# main.net
KiCad netlist of a schematic drawn in Altium Designer
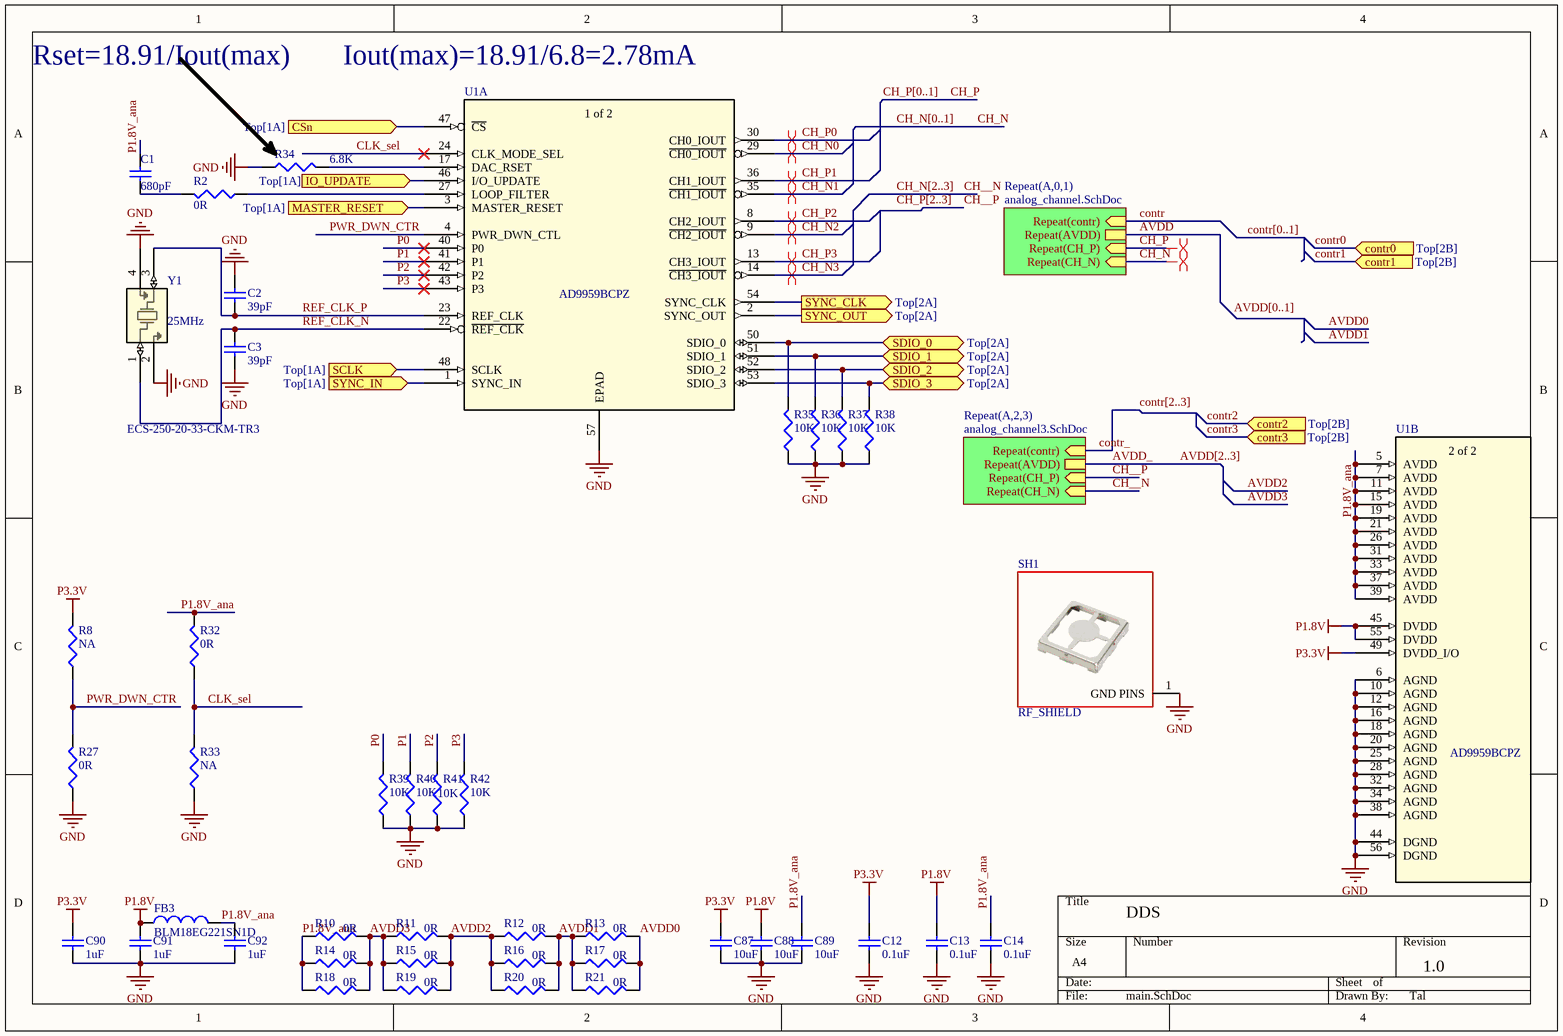
[diagram p0: main.SchDoc]

(export (version "E")
  (design (tool "Eeschema 10.0.6"))
  (components
    (comp (ref "C1")
      (value "680pF 50V")
      (footprint "C0402")
      (description "CAP CER 680PF 50V NP0 0402")
      (fields
        (field (name "MANUFACTURER PART NUMBER") "C1005C0G1H6R8D")
        (field (name "MANUFACTURER") "TDK Corporation")
        (field (name "CAPACITANCE") "680pF")
      )
      (libsource (lib "L_SCH_C") (part "CAP CER 6.8pF 50V NP0 0402"))
    )
    (comp (ref "C2")
      (value "39pF 50V")
      (footprint "C0402")
      (description "CAP CER 39PF 50V NP0 0402")
      (fields
        (field (name "MANUFACTURER PART NUMBER") "C1005C0G1H6R8D")
        (field (name "MANUFACTURER") "TDK Corporation")
        (field (name "CAPACITANCE") "39pF")
      )
      (libsource (lib "L_SCH_C") (part "CAP CER 6.8pF 50V NP0 0402"))
    )
    (comp (ref "C3")
      (value "39pF 50V")
      (footprint "C0402")
      (description "CAP CER 39PF 50V NP0 0402")
      (fields
        (field (name "MANUFACTURER PART NUMBER") "C1005C0G1H6R8D")
        (field (name "MANUFACTURER") "TDK Corporation")
        (field (name "CAPACITANCE") "39pF")
      )
      (libsource (lib "L_SCH_C") (part "CAP CER 6.8pF 50V NP0 0402"))
    )
    (comp (ref "C12")
      (value "0.1uF 50V")
      (footprint "C0402")
      (description "CAP CER 0.1uF 50V NP0 0402")
      (fields
        (field (name "MANUFACTURER PART NUMBER") "C1005C0G1H6R8D")
        (field (name "MANUFACTURER") "TDK Corporation")
        (field (name "CAPACITANCE") "0.1uF")
      )
      (libsource (lib "L_SCH_C") (part "CAP CER 6.8pF 50V NP0 0402"))
    )
    (comp (ref "C13")
      (value "0.1uF 50V")
      (footprint "C0402")
      (description "CAP CER 0.1uF 50V NP0 0402")
      (fields
        (field (name "MANUFACTURER PART NUMBER") "C1005C0G1H6R8D")
        (field (name "MANUFACTURER") "TDK Corporation")
        (field (name "CAPACITANCE") "0.1uF")
      )
      (libsource (lib "L_SCH_C") (part "CAP CER 6.8pF 50V NP0 0402"))
    )
    (comp (ref "C14")
      (value "0.1uF 50V")
      (footprint "C0402")
      (description "CAP CER 0.1uF 50V NP0 0402")
      (fields
        (field (name "MANUFACTURER PART NUMBER") "C1005C0G1H6R8D")
        (field (name "MANUFACTURER") "TDK Corporation")
        (field (name "CAPACITANCE") "0.1uF")
      )
      (libsource (lib "L_SCH_C") (part "CAP CER 6.8pF 50V NP0 0402"))
    )
    (comp (ref "C87")
      (value "10uF 10V")
      (footprint "C0402")
      (description "CAP CER 10uF 10V X5R 0402")
      (fields
        (field (name "MANUFACTURER PART NUMBER") "C1005C0G1H6R8D")
        (field (name "MANUFACTURER") "TDK Corporation")
        (field (name "CAPACITANCE") "10uF")
      )
      (libsource (lib "L_SCH_C") (part "CAP CER 6.8pF 50V NP0 0402"))
    )
    (comp (ref "C88")
      (value "10uF 10V")
      (footprint "C0402")
      (description "CAP CER 10uF 10V X5R 0402")
      (fields
        (field (name "MANUFACTURER PART NUMBER") "C1005C0G1H6R8D")
        (field (name "MANUFACTURER") "TDK Corporation")
        (field (name "CAPACITANCE") "10uF")
      )
      (libsource (lib "L_SCH_C") (part "CAP CER 6.8pF 50V NP0 0402"))
    )
    (comp (ref "C89")
      (value "10uF 10V")
      (footprint "C0402")
      (description "CAP CER 10uF 10V X5R 0402")
      (fields
        (field (name "MANUFACTURER PART NUMBER") "C1005C0G1H6R8D")
        (field (name "MANUFACTURER") "TDK Corporation")
        (field (name "CAPACITANCE") "10uF")
      )
      (libsource (lib "L_SCH_C") (part "CAP CER 6.8pF 50V NP0 0402"))
    )
    (comp (ref "C90")
      (value "1uF 25V")
      (footprint "C0402")
      (description "CAP CER 1uF 25V X5R 0402")
      (fields
        (field (name "MANUFACTURER PART NUMBER") "C1005C0G1H6R8D")
        (field (name "MANUFACTURER") "TDK Corporation")
        (field (name "CAPACITANCE") "1uF")
      )
      (libsource (lib "L_SCH_C") (part "CAP CER 6.8pF 50V NP0 0402"))
    )
    (comp (ref "C91")
      (value "1uF 25V")
      (footprint "C0402")
      (description "CAP CER 1uF 25V X5R 0402")
      (fields
        (field (name "MANUFACTURER PART NUMBER") "C1005C0G1H6R8D")
        (field (name "MANUFACTURER") "TDK Corporation")
        (field (name "CAPACITANCE") "1uF")
      )
      (libsource (lib "L_SCH_C") (part "CAP CER 6.8pF 50V NP0 0402"))
    )
    (comp (ref "C92")
      (value "1uF 25V")
      (footprint "C0402")
      (description "CAP CER 1uF 25V X5R 0402")
      (fields
        (field (name "MANUFACTURER PART NUMBER") "C1005C0G1H6R8D")
        (field (name "MANUFACTURER") "TDK Corporation")
        (field (name "CAPACITANCE") "1uF")
      )
      (libsource (lib "L_SCH_C") (part "CAP CER 6.8pF 50V NP0 0402"))
    )
    (comp (ref "FB3")
      (value "BLM18EG221SN1D")
      (footprint "fb0603")
      (description "FERRITE BEAD 220_OHM@100MHz 0603 2A 50mohm_DC")
      (fields
        (field (name "MANUFACTURER") "Taiyo Yuden")
        (field (name "MANUFACTURER PART NUMBER") "BLM18EG221SN1D")
      )
      (libsource (lib "L_SCH") (part "BK1608HS600-T"))
    )
    (comp (ref "R2")
      (value "0R")
      (footprint "R0402")
      (description "RES 0 OHM 1/10W 1% 0402 SMD")
      (fields
        (field (name "MANUFACTURER PART NUMBER") "ERJ-2RKF1000X")
        (field (name "MANUFACTURER") "Panasonic Electronic Components")
      )
      (libsource (lib "L_SCH_R") (part "RES 100 OHM 1/10W 1% 0402 SMD"))
    )
    (comp (ref "R8")
      (value "NA")
      (footprint "R0402")
      (description "RES 0 OHM 1/10W 1% 0402 SMD")
      (fields
        (field (name "MANUFACTURER PART NUMBER") "ERJ-2RKF1000X")
        (field (name "MANUFACTURER") "Panasonic Electronic Components")
      )
      (libsource (lib "L_SCH_R") (part "RES 100 OHM 1/10W 1% 0402 SMD"))
    )
    (comp (ref "R10")
      (value "0R")
      (footprint "R0805")
      (description "RES 0 OHM 1/8W 1% 0805 SMD")
      (fields
        (field (name "MANUFACTURER PART NUMBER") "RMCF0805FT200R")
        (field (name "MANUFACTURER") "Stackpole Electronics Inc")
      )
      (libsource (lib "L_SCH_R") (part "RES 200 OHM 1/8W 1% 0805 SMD"))
    )
    (comp (ref "R11")
      (value "0R")
      (footprint "R0805")
      (description "RES 0 OHM 1/8W 1% 0805 SMD")
      (fields
        (field (name "MANUFACTURER PART NUMBER") "RMCF0805FT200R")
        (field (name "MANUFACTURER") "Stackpole Electronics Inc")
      )
      (libsource (lib "L_SCH_R") (part "RES 200 OHM 1/8W 1% 0805 SMD"))
    )
    (comp (ref "R12")
      (value "0R")
      (footprint "R0805")
      (description "RES 0 OHM 1/8W 1% 0805 SMD")
      (fields
        (field (name "MANUFACTURER PART NUMBER") "RMCF0805FT200R")
        (field (name "MANUFACTURER") "Stackpole Electronics Inc")
      )
      (libsource (lib "L_SCH_R") (part "RES 200 OHM 1/8W 1% 0805 SMD"))
    )
    (comp (ref "R13")
      (value "0R")
      (footprint "R0805")
      (description "RES 0 OHM 1/8W 1% 0805 SMD")
      (fields
        (field (name "MANUFACTURER PART NUMBER") "RMCF0805FT200R")
        (field (name "MANUFACTURER") "Stackpole Electronics Inc")
      )
      (libsource (lib "L_SCH_R") (part "RES 200 OHM 1/8W 1% 0805 SMD"))
    )
    (comp (ref "R14")
      (value "0R")
      (footprint "R0805")
      (description "RES 0 OHM 1/8W 1% 0805 SMD")
      (fields
        (field (name "MANUFACTURER PART NUMBER") "RMCF0805FT200R")
        (field (name "MANUFACTURER") "Stackpole Electronics Inc")
      )
      (libsource (lib "L_SCH_R") (part "RES 200 OHM 1/8W 1% 0805 SMD"))
    )
    (comp (ref "R15")
      (value "0R")
      (footprint "R0805")
      (description "RES 0 OHM 1/8W 1% 0805 SMD")
      (fields
        (field (name "MANUFACTURER PART NUMBER") "RMCF0805FT200R")
        (field (name "MANUFACTURER") "Stackpole Electronics Inc")
      )
      (libsource (lib "L_SCH_R") (part "RES 200 OHM 1/8W 1% 0805 SMD"))
    )
    (comp (ref "R16")
      (value "0R")
      (footprint "R0805")
      (description "RES 0 OHM 1/8W 1% 0805 SMD")
      (fields
        (field (name "MANUFACTURER PART NUMBER") "RMCF0805FT200R")
        (field (name "MANUFACTURER") "Stackpole Electronics Inc")
      )
      (libsource (lib "L_SCH_R") (part "RES 200 OHM 1/8W 1% 0805 SMD"))
    )
    (comp (ref "R17")
      (value "0R")
      (footprint "R0805")
      (description "RES 0 OHM 1/8W 1% 0805 SMD")
      (fields
        (field (name "MANUFACTURER PART NUMBER") "RMCF0805FT200R")
        (field (name "MANUFACTURER") "Stackpole Electronics Inc")
      )
      (libsource (lib "L_SCH_R") (part "RES 200 OHM 1/8W 1% 0805 SMD"))
    )
    (comp (ref "R18")
      (value "0R")
      (footprint "R0805")
      (description "RES 0 OHM 1/8W 1% 0805 SMD")
      (fields
        (field (name "MANUFACTURER PART NUMBER") "RMCF0805FT200R")
        (field (name "MANUFACTURER") "Stackpole Electronics Inc")
      )
      (libsource (lib "L_SCH_R") (part "RES 200 OHM 1/8W 1% 0805 SMD"))
    )
    (comp (ref "R19")
      (value "0R")
      (footprint "R0805")
      (description "RES 0 OHM 1/8W 1% 0805 SMD")
      (fields
        (field (name "MANUFACTURER PART NUMBER") "RMCF0805FT200R")
        (field (name "MANUFACTURER") "Stackpole Electronics Inc")
      )
      (libsource (lib "L_SCH_R") (part "RES 200 OHM 1/8W 1% 0805 SMD"))
    )
    (comp (ref "R20")
      (value "0R")
      (footprint "R0805")
      (description "RES 0 OHM 1/8W 1% 0805 SMD")
      (fields
        (field (name "MANUFACTURER PART NUMBER") "RMCF0805FT200R")
        (field (name "MANUFACTURER") "Stackpole Electronics Inc")
      )
      (libsource (lib "L_SCH_R") (part "RES 200 OHM 1/8W 1% 0805 SMD"))
    )
    (comp (ref "R21")
      (value "0R")
      (footprint "R0805")
      (description "RES 0 OHM 1/8W 1% 0805 SMD")
      (fields
        (field (name "MANUFACTURER PART NUMBER") "RMCF0805FT200R")
        (field (name "MANUFACTURER") "Stackpole Electronics Inc")
      )
      (libsource (lib "L_SCH_R") (part "RES 200 OHM 1/8W 1% 0805 SMD"))
    )
    (comp (ref "R27")
      (value "0R")
      (footprint "R0402")
      (description "RES 0 OHM 1/10W 1% 0402 SMD")
      (fields
        (field (name "MANUFACTURER PART NUMBER") "ERJ-2RKF1000X")
        (field (name "MANUFACTURER") "Panasonic Electronic Components")
      )
      (libsource (lib "L_SCH_R") (part "RES 100 OHM 1/10W 1% 0402 SMD"))
    )
    (comp (ref "R32")
      (value "0R")
      (footprint "R0402")
      (description "RES 0 OHM 1/10W 1% 0402 SMD")
      (fields
        (field (name "MANUFACTURER PART NUMBER") "ERJ-2RKF1000X")
        (field (name "MANUFACTURER") "Panasonic Electronic Components")
      )
      (libsource (lib "L_SCH_R") (part "RES 100 OHM 1/10W 1% 0402 SMD"))
    )
    (comp (ref "R33")
      (value "NA")
      (footprint "R0402")
      (description "RES 0 OHM 1/10W 1% 0402 SMD")
      (fields
        (field (name "MANUFACTURER PART NUMBER") "ERJ-2RKF1000X")
        (field (name "MANUFACTURER") "Panasonic Electronic Components")
      )
      (libsource (lib "L_SCH_R") (part "RES 100 OHM 1/10W 1% 0402 SMD"))
    )
    (comp (ref "R34")
      (value "6.8K")
      (footprint "R0402")
      (description "RES 6.8K OHM 1/16W 1% 0402")
      (fields
        (field (name "MANUFACTURER PART NUMBER") "RMCF0402FT3K09")
        (field (name "MANUFACTURER") "Stackpole Electronics Inc")
      )
      (libsource (lib "L_SCH_R") (part "RES 3.09K OHM 1/16W 1% 0402"))
    )
    (comp (ref "R35")
      (value "10K")
      (footprint "R0402")
      (description "RES 10K OHM 1/16W 1% 0402")
      (fields
        (field (name "MANUFACTURER PART NUMBER") "RMCF0402FT3K09")
        (field (name "MANUFACTURER") "Stackpole Electronics Inc")
      )
      (libsource (lib "L_SCH_R") (part "RES 3.09K OHM 1/16W 1% 0402"))
    )
    (comp (ref "R36")
      (value "10K")
      (footprint "R0402")
      (description "RES 10K OHM 1/16W 1% 0402")
      (fields
        (field (name "MANUFACTURER PART NUMBER") "RMCF0402FT3K09")
        (field (name "MANUFACTURER") "Stackpole Electronics Inc")
      )
      (libsource (lib "L_SCH_R") (part "RES 3.09K OHM 1/16W 1% 0402"))
    )
    (comp (ref "R37")
      (value "10K")
      (footprint "R0402")
      (description "RES 10K OHM 1/16W 1% 0402")
      (fields
        (field (name "MANUFACTURER PART NUMBER") "RMCF0402FT3K09")
        (field (name "MANUFACTURER") "Stackpole Electronics Inc")
      )
      (libsource (lib "L_SCH_R") (part "RES 3.09K OHM 1/16W 1% 0402"))
    )
    (comp (ref "R38")
      (value "10K")
      (footprint "R0402")
      (description "RES 10K OHM 1/16W 1% 0402")
      (fields
        (field (name "MANUFACTURER PART NUMBER") "RMCF0402FT3K09")
        (field (name "MANUFACTURER") "Stackpole Electronics Inc")
      )
      (libsource (lib "L_SCH_R") (part "RES 3.09K OHM 1/16W 1% 0402"))
    )
    (comp (ref "R39")
      (value "10K")
      (footprint "R0402")
      (description "RES 10K OHM 1/16W 1% 0402")
      (fields
        (field (name "MANUFACTURER PART NUMBER") "RMCF0402FT3K09")
        (field (name "MANUFACTURER") "Stackpole Electronics Inc")
      )
      (libsource (lib "L_SCH_R") (part "RES 3.09K OHM 1/16W 1% 0402"))
    )
    (comp (ref "R40")
      (value "10K")
      (footprint "R0402")
      (description "RES 10K OHM 1/16W 1% 0402")
      (fields
        (field (name "MANUFACTURER PART NUMBER") "RMCF0402FT3K09")
        (field (name "MANUFACTURER") "Stackpole Electronics Inc")
      )
      (libsource (lib "L_SCH_R") (part "RES 3.09K OHM 1/16W 1% 0402"))
    )
    (comp (ref "R41")
      (value "10K")
      (footprint "R0402")
      (description "RES 10K OHM 1/16W 1% 0402")
      (fields
        (field (name "MANUFACTURER PART NUMBER") "RMCF0402FT3K09")
        (field (name "MANUFACTURER") "Stackpole Electronics Inc")
      )
      (libsource (lib "L_SCH_R") (part "RES 3.09K OHM 1/16W 1% 0402"))
    )
    (comp (ref "R42")
      (value "10K")
      (footprint "R0402")
      (description "RES 10K OHM 1/16W 1% 0402")
      (fields
        (field (name "MANUFACTURER PART NUMBER") "RMCF0402FT3K09")
        (field (name "MANUFACTURER") "Stackpole Electronics Inc")
      )
      (libsource (lib "L_SCH_R") (part "RES 3.09K OHM 1/16W 1% 0402"))
    )
    (comp (ref "SH1")
      (value "RF_SHIELD")
      (footprint "SMS201F")
      (description "RF SHIELD 0.5\" X 0.538\" SMD")
      (fields
        (field (name "MANUFACTURER_PART_NUMBER") "SMS-201F")
        (field (name "MANUFACTURER") "Leader Tech Inc.")
      )
      (libsource (lib "DDS_PCB_1") (part "RF_SHIELD"))
    )
    (comp (ref "U1")
      (value "AD9959BCPZ")
      (footprint "CP_56_1_ADI")
      (description "No Description Available")
      (fields (field (name "COPYRIGHT") "Copyright (C) 2023 Ultra Librarian. All rights reserved."))
      (libsource (lib "AD9959BCPZ") (part "AD9959BCPZ"))
    )
    (comp (ref "Y1")
      (value "ECS-250-20-33-CKM-TR3")
      (footprint "SMD4_ECX-32_3p2x2p5_ECS")
      (description "No Description Available")
      (fields (field (name "COPYRIGHT") "Copyright (C) 2023 Ultra Librarian. All rights reserved."))
      (libsource (lib "ECS-250-20-33-CKM-TR3") (part "ECS-250-20-33-CKM-TR3"))
    )
  )
  (nets
    (net (code "2") (name "/AVDD0") (class "Default")
      (node (ref "R13") (pin "2") (pinfunction "2_2") (pintype "passive"))
      (node (ref "R17") (pin "2") (pinfunction "2_2") (pintype "passive"))
      (node (ref "R21") (pin "2") (pinfunction "2_2") (pintype "passive"))
    )
    (net (code "3") (name "/AVDD1") (class "Default")
      (node (ref "R12") (pin "2") (pinfunction "2_2") (pintype "passive"))
      (node (ref "R13") (pin "1") (pinfunction "1_1") (pintype "passive"))
      (node (ref "R16") (pin "2") (pinfunction "2_2") (pintype "passive"))
      (node (ref "R17") (pin "1") (pinfunction "1_1") (pintype "passive"))
      (node (ref "R20") (pin "2") (pinfunction "2_2") (pintype "passive"))
      (node (ref "R21") (pin "1") (pinfunction "1_1") (pintype "passive"))
    )
    (net (code "4") (name "/AVDD2") (class "Default")
      (node (ref "R11") (pin "2") (pinfunction "2_2") (pintype "passive"))
      (node (ref "R12") (pin "1") (pinfunction "1_1") (pintype "passive"))
      (node (ref "R15") (pin "2") (pinfunction "2_2") (pintype "passive"))
      (node (ref "R16") (pin "1") (pinfunction "1_1") (pintype "passive"))
      (node (ref "R19") (pin "2") (pinfunction "2_2") (pintype "passive"))
      (node (ref "R20") (pin "1") (pinfunction "1_1") (pintype "passive"))
    )
    (net (code "5") (name "/AVDD3") (class "Default")
      (node (ref "R10") (pin "2") (pinfunction "2_2") (pintype "passive"))
      (node (ref "R11") (pin "1") (pinfunction "1_1") (pintype "passive"))
      (node (ref "R14") (pin "2") (pinfunction "2_2") (pintype "passive"))
      (node (ref "R15") (pin "1") (pinfunction "1_1") (pintype "passive"))
      (node (ref "R18") (pin "2") (pinfunction "2_2") (pintype "passive"))
      (node (ref "R19") (pin "1") (pinfunction "1_1") (pintype "passive"))
    )
    (net (code "9") (name "/CH_N0") (class "Default")
      (node (ref "U1") (pin "29") (pinfunction "~{CH0_IOUT}_29") (pintype "output"))
    )
    (net (code "10") (name "/CH_N1") (class "Default")
      (node (ref "U1") (pin "35") (pinfunction "~{CH1_IOUT}_35") (pintype "output"))
    )
    (net (code "11") (name "/CH_N2") (class "Default")
      (node (ref "U1") (pin "9") (pinfunction "~{CH2_IOUT}_9") (pintype "output"))
    )
    (net (code "12") (name "/CH_N3") (class "Default")
      (node (ref "U1") (pin "14") (pinfunction "~{CH3_IOUT}_14") (pintype "output"))
    )
    (net (code "16") (name "/CH_P0") (class "Default")
      (node (ref "U1") (pin "30") (pinfunction "CH0_IOUT_30") (pintype "output"))
    )
    (net (code "17") (name "/CH_P1") (class "Default")
      (node (ref "U1") (pin "36") (pinfunction "CH1_IOUT_36") (pintype "output"))
    )
    (net (code "18") (name "/CH_P2") (class "Default")
      (node (ref "U1") (pin "8") (pinfunction "CH2_IOUT_8") (pintype "output"))
    )
    (net (code "19") (name "/CH_P3") (class "Default")
      (node (ref "U1") (pin "13") (pinfunction "CH3_IOUT_13") (pintype "output"))
    )
    (net (code "24") (name "/CLK_sel") (class "Default")
      (node (ref "R32") (pin "1") (pinfunction "1_1") (pintype "passive"))
      (node (ref "R33") (pin "2") (pinfunction "2_2") (pintype "passive"))
      (node (ref "U1") (pin "24") (pinfunction "CLK_MODE_SEL_24") (pintype "input"))
    )
    (net (code "25") (name "/CSn") (class "Default")
      (node (ref "U1") (pin "47") (pinfunction "~{CS}_47") (pintype "input"))
    )
    (net (code "26") (name "/IO_UPDATE") (class "Default")
      (node (ref "U1") (pin "46") (pinfunction "I/O_UPDATE_46") (pintype "input"))
    )
    (net (code "27") (name "/MASTER_RESET") (class "Default")
      (node (ref "U1") (pin "3") (pinfunction "MASTER_RESET_3") (pintype "input"))
    )
    (net (code "28") (name "/P0") (class "Default")
      (node (ref "R39") (pin "2") (pinfunction "2_2") (pintype "passive"))
      (node (ref "U1") (pin "40") (pinfunction "P0_40") (pintype "input"))
    )
    (net (code "29") (name "/P1") (class "Default")
      (node (ref "R40") (pin "2") (pinfunction "2_2") (pintype "passive"))
      (node (ref "U1") (pin "41") (pinfunction "P1_41") (pintype "input"))
    )
    (net (code "30") (name "/P1.8V_ana") (class "Default")
      (node (ref "C1") (pin "1") (pinfunction "1_1") (pintype "passive"))
      (node (ref "C14") (pin "2") (pinfunction "2_2") (pintype "passive"))
      (node (ref "C89") (pin "2") (pinfunction "2_2") (pintype "passive"))
      (node (ref "C92") (pin "2") (pinfunction "2_2") (pintype "passive"))
      (node (ref "FB3") (pin "2") (pinfunction "2_2") (pintype "passive"))
      (node (ref "R10") (pin "1") (pinfunction "1_1") (pintype "passive"))
      (node (ref "R14") (pin "1") (pinfunction "1_1") (pintype "passive"))
      (node (ref "R18") (pin "1") (pinfunction "1_1") (pintype "passive"))
      (node (ref "R32") (pin "2") (pinfunction "2_2") (pintype "passive"))
      (node (ref "U1") (pin "11") (pinfunction "AVDD_11") (pintype "input"))
      (node (ref "U1") (pin "15") (pinfunction "AVDD_15") (pintype "input"))
      (node (ref "U1") (pin "19") (pinfunction "AVDD_19") (pintype "input"))
      (node (ref "U1") (pin "21") (pinfunction "AVDD_21") (pintype "input"))
      (node (ref "U1") (pin "26") (pinfunction "AVDD_26") (pintype "input"))
      (node (ref "U1") (pin "31") (pinfunction "AVDD_31") (pintype "input"))
      (node (ref "U1") (pin "33") (pinfunction "AVDD_33") (pintype "input"))
      (node (ref "U1") (pin "37") (pinfunction "AVDD_37") (pintype "input"))
      (node (ref "U1") (pin "39") (pinfunction "AVDD_39") (pintype "input"))
      (node (ref "U1") (pin "5") (pinfunction "AVDD_5") (pintype "input"))
      (node (ref "U1") (pin "7") (pinfunction "AVDD_7") (pintype "input"))
    )
    (net (code "31") (name "/P2") (class "Default")
      (node (ref "R41") (pin "2") (pinfunction "2_2") (pintype "passive"))
      (node (ref "U1") (pin "42") (pinfunction "P2_42") (pintype "input"))
    )
    (net (code "32") (name "/P3") (class "Default")
      (node (ref "R42") (pin "2") (pinfunction "2_2") (pintype "passive"))
      (node (ref "U1") (pin "43") (pinfunction "P3_43") (pintype "input"))
    )
    (net (code "33") (name "/PWR_DWN_CTR") (class "Default")
      (node (ref "R27") (pin "2") (pinfunction "2_2") (pintype "passive"))
      (node (ref "R8") (pin "1") (pinfunction "1_1") (pintype "passive"))
      (node (ref "U1") (pin "4") (pinfunction "PWR_DWN_CTL_4") (pintype "input"))
    )
    (net (code "34") (name "/REF_CLK_N") (class "Default")
      (node (ref "C3") (pin "2") (pinfunction "2_2") (pintype "passive"))
      (node (ref "U1") (pin "22") (pinfunction "~{REF_CLK}_22") (pintype "input"))
      (node (ref "Y1") (pin "1") (pinfunction "1_1") (pintype "bidirectional"))
    )
    (net (code "35") (name "/REF_CLK_P") (class "Default")
      (node (ref "C2") (pin "1") (pinfunction "1_1") (pintype "passive"))
      (node (ref "U1") (pin "23") (pinfunction "REF_CLK_23") (pintype "input"))
      (node (ref "Y1") (pin "3") (pinfunction "3_3") (pintype "bidirectional"))
    )
    (net (code "36") (name "/SCLK") (class "Default")
      (node (ref "U1") (pin "48") (pinfunction "SCLK_48") (pintype "input"))
    )
    (net (code "37") (name "/SDIO_0") (class "Default")
      (node (ref "R35") (pin "2") (pinfunction "2_2") (pintype "passive"))
      (node (ref "U1") (pin "50") (pinfunction "SDIO_0_50") (pintype "bidirectional"))
    )
    (net (code "38") (name "/SDIO_1") (class "Default")
      (node (ref "R36") (pin "2") (pinfunction "2_2") (pintype "passive"))
      (node (ref "U1") (pin "51") (pinfunction "SDIO_1_51") (pintype "bidirectional"))
    )
    (net (code "39") (name "/SDIO_2") (class "Default")
      (node (ref "R37") (pin "2") (pinfunction "2_2") (pintype "passive"))
      (node (ref "U1") (pin "52") (pinfunction "SDIO_2_52") (pintype "bidirectional"))
    )
    (net (code "40") (name "/SDIO_3") (class "Default")
      (node (ref "R38") (pin "2") (pinfunction "2_2") (pintype "passive"))
      (node (ref "U1") (pin "53") (pinfunction "SDIO_3_53") (pintype "bidirectional"))
    )
    (net (code "41") (name "/SYNC_CLK") (class "Default")
      (node (ref "U1") (pin "54") (pinfunction "SYNC_CLK_54") (pintype "output"))
    )
    (net (code "42") (name "/SYNC_IN") (class "Default")
      (node (ref "U1") (pin "1") (pinfunction "SYNC_IN_1") (pintype "input"))
    )
    (net (code "43") (name "/SYNC_OUT") (class "Default")
      (node (ref "U1") (pin "2") (pinfunction "SYNC_OUT_2") (pintype "output"))
    )
    (net (code "51") (name "GND") (class "Default")
      (node (ref "C12") (pin "1") (pinfunction "1_1") (pintype "passive"))
      (node (ref "C13") (pin "1") (pinfunction "1_1") (pintype "passive"))
      (node (ref "C14") (pin "1") (pinfunction "1_1") (pintype "passive"))
      (node (ref "C2") (pin "2") (pinfunction "2_2") (pintype "passive"))
      (node (ref "C3") (pin "1") (pinfunction "1_1") (pintype "passive"))
      (node (ref "C87") (pin "1") (pinfunction "1_1") (pintype "passive"))
      (node (ref "C88") (pin "1") (pinfunction "1_1") (pintype "passive"))
      (node (ref "C89") (pin "1") (pinfunction "1_1") (pintype "passive"))
      (node (ref "C90") (pin "1") (pinfunction "1_1") (pintype "passive"))
      (node (ref "C91") (pin "1") (pinfunction "1_1") (pintype "passive"))
      (node (ref "C92") (pin "1") (pinfunction "1_1") (pintype "passive"))
      (node (ref "R27") (pin "1") (pinfunction "1_1") (pintype "passive"))
      (node (ref "R33") (pin "1") (pinfunction "1_1") (pintype "passive"))
      (node (ref "R34") (pin "1") (pinfunction "1_1") (pintype "passive"))
      (node (ref "R35") (pin "1") (pinfunction "1_1") (pintype "passive"))
      (node (ref "R36") (pin "1") (pinfunction "1_1") (pintype "passive"))
      (node (ref "R37") (pin "1") (pinfunction "1_1") (pintype "passive"))
      (node (ref "R38") (pin "1") (pinfunction "1_1") (pintype "passive"))
      (node (ref "R39") (pin "1") (pinfunction "1_1") (pintype "passive"))
      (node (ref "R40") (pin "1") (pinfunction "1_1") (pintype "passive"))
      (node (ref "R41") (pin "1") (pinfunction "1_1") (pintype "passive"))
      (node (ref "R42") (pin "1") (pinfunction "1_1") (pintype "passive"))
      (node (ref "SH1") (pin "1") (pinfunction "GND_PINS_1") (pintype "passive"))
      (node (ref "U1") (pin "10") (pinfunction "AGND_10") (pintype "input"))
      (node (ref "U1") (pin "12") (pinfunction "AGND_12") (pintype "input"))
      (node (ref "U1") (pin "16") (pinfunction "AGND_16") (pintype "input"))
      (node (ref "U1") (pin "18") (pinfunction "AGND_18") (pintype "input"))
      (node (ref "U1") (pin "20") (pinfunction "AGND_20") (pintype "input"))
      (node (ref "U1") (pin "25") (pinfunction "AGND_25") (pintype "input"))
      (node (ref "U1") (pin "28") (pinfunction "AGND_28") (pintype "input"))
      (node (ref "U1") (pin "32") (pinfunction "AGND_32") (pintype "input"))
      (node (ref "U1") (pin "34") (pinfunction "AGND_34") (pintype "input"))
      (node (ref "U1") (pin "38") (pinfunction "AGND_38") (pintype "input"))
      (node (ref "U1") (pin "44") (pinfunction "DGND_44") (pintype "input"))
      (node (ref "U1") (pin "56") (pinfunction "DGND_56") (pintype "input"))
      (node (ref "U1") (pin "57") (pinfunction "EPAD_57") (pintype "passive"))
      (node (ref "U1") (pin "6") (pinfunction "AGND_6") (pintype "input"))
      (node (ref "Y1") (pin "2") (pinfunction "2_2") (pintype "passive"))
      (node (ref "Y1") (pin "4") (pinfunction "4_4") (pintype "passive"))
    )
    (net (code "52") (name "Net-(C1-Pad2)") (class "Default")
      (node (ref "C1") (pin "2") (pinfunction "2_2") (pintype "passive"))
      (node (ref "R2") (pin "2") (pinfunction "2_2") (pintype "passive"))
    )
    (net (code "53") (name "Net-(U1A-DAC_RSET)") (class "Default")
      (node (ref "R34") (pin "2") (pinfunction "2_2") (pintype "passive"))
      (node (ref "U1") (pin "17") (pinfunction "DAC_RSET_17") (pintype "input"))
    )
    (net (code "54") (name "Net-(U1A-LOOP_FILTER)") (class "Default")
      (node (ref "R2") (pin "1") (pinfunction "1_1") (pintype "passive"))
      (node (ref "U1") (pin "27") (pinfunction "LOOP_FILTER_27") (pintype "input"))
    )
    (net (code "55") (name "P1.8V") (class "Default")
      (node (ref "C13") (pin "2") (pinfunction "2_2") (pintype "passive"))
      (node (ref "C88") (pin "2") (pinfunction "2_2") (pintype "passive"))
      (node (ref "C91") (pin "2") (pinfunction "2_2") (pintype "passive"))
      (node (ref "FB3") (pin "1") (pinfunction "1_1") (pintype "passive"))
      (node (ref "U1") (pin "45") (pinfunction "DVDD_45") (pintype "input"))
      (node (ref "U1") (pin "55") (pinfunction "DVDD_55") (pintype "input"))
    )
    (net (code "56") (name "P3.3V") (class "Default")
      (node (ref "C12") (pin "2") (pinfunction "2_2") (pintype "passive"))
      (node (ref "C87") (pin "2") (pinfunction "2_2") (pintype "passive"))
      (node (ref "C90") (pin "2") (pinfunction "2_2") (pintype "passive"))
      (node (ref "R8") (pin "2") (pinfunction "2_2") (pintype "passive"))
      (node (ref "U1") (pin "49") (pinfunction "DVDD_I/O_49") (pintype "input"))
    )
  )
)
